# BRTPOT_SHEET.net
KiCad netlist of a schematic drawn in Altium Designer
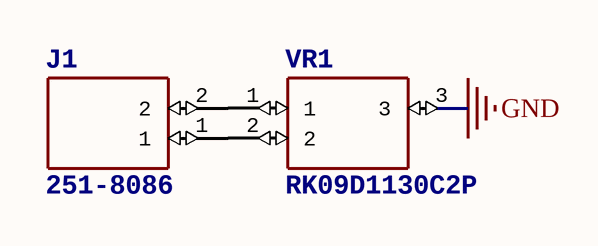
[diagram p0: BRTPOT_SHEET.SchDoc]

(export (version "E")
  (design (tool "Eeschema 10.0.6"))
  (components
    (comp (ref "J1") (value "251-8086") (footprint "2518086") (libsource (lib "251-8086") (part "251-8086")))
    (comp (ref "VR1")
      (value "RK09D1130C2P")
      (footprint "RK09D1130C3C")
      (fields (field (name "MOUSER_PART_NUMBER") "688-RK09D1130C2P"))
      (libsource (lib "729-3640") (part "RK09D1130C2P"))
    )
  )
  (nets
    (net (code "1") (name "GND") (class "Default")
      (node (ref "VR1") (pin "3") (pinfunction "3_3") (pintype "bidirectional"))
    )
    (net (code "2") (name "Net-(J1-Pad1)") (class "Default")
      (node (ref "J1") (pin "1") (pinfunction "1_1") (pintype "bidirectional"))
      (node (ref "VR1") (pin "2") (pinfunction "2_2") (pintype "bidirectional"))
    )
    (net (code "3") (name "Net-(J1-Pad2)") (class "Default")
      (node (ref "J1") (pin "2") (pinfunction "2_2") (pintype "bidirectional"))
      (node (ref "VR1") (pin "1") (pinfunction "1_1") (pintype "bidirectional"))
    )
  )
)
